# billdetect_ring2.net
KiCad netlist of a schematic drawn in EAGLE
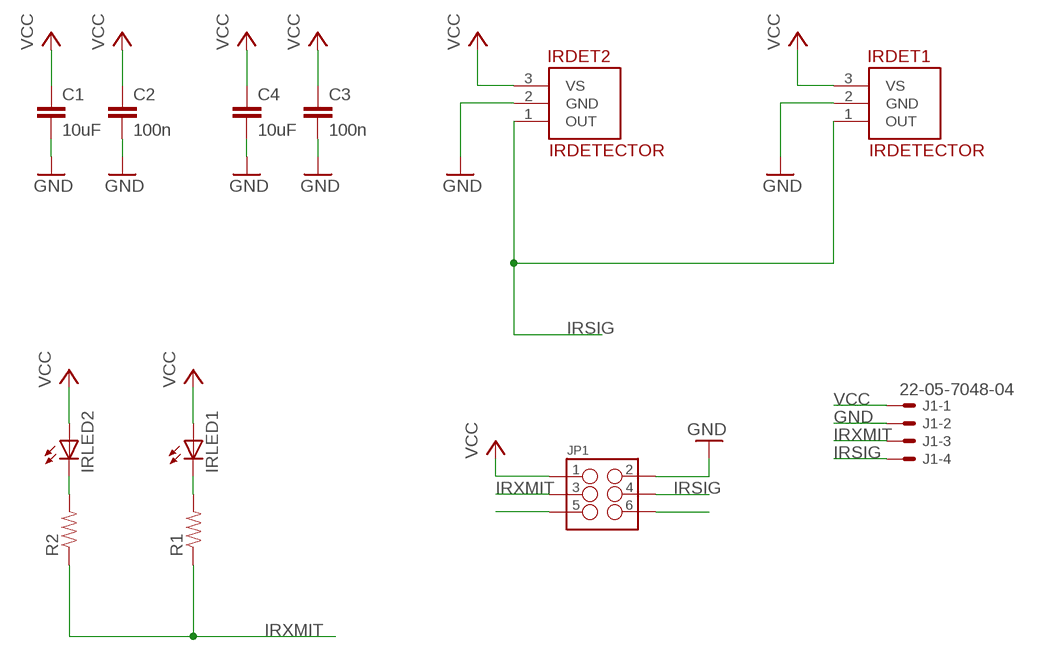
[diagram p0: schematic, sheet 1]

(export (version "E")
  (design (tool "Eeschema 10.0.6"))
  (components
    (comp (ref "C1")
      (value "10uF")
      (footprint "eagle-import:0805")
      (libsource (lib "eagle-import") (part "CAP0805"))
    )
    (comp (ref "C2")
      (value "100n")
      (footprint "eagle-import:0805")
      (libsource (lib "eagle-import") (part "CAP0805"))
    )
    (comp (ref "C3")
      (value "100n")
      (footprint "eagle-import:0805")
      (libsource (lib "eagle-import") (part "CAP0805"))
    )
    (comp (ref "C4")
      (value "10uF")
      (footprint "eagle-import:0805")
      (libsource (lib "eagle-import") (part "CAP0805"))
    )
    (comp (ref "IRDET1")
      (value "IRDETECTOR")
      (footprint "eagle-import:TSOP-3PIN-2.54MM")
      (libsource (lib "eagle-import") (part "IRDETECTOR"))
    )
    (comp (ref "IRDET2")
      (value "IRDETECTOR")
      (footprint "eagle-import:TSOP-3PIN-2.54MM")
      (libsource (lib "eagle-import") (part "IRDETECTOR"))
    )
    (comp (ref "IRLED1")
      (value "LED-5MM-90DEG")
      (footprint "eagle-import:LED-5MM-90DEG")
      (libsource (lib "eagle-import") (part "LED-5MM-90DEG"))
    )
    (comp (ref "IRLED2")
      (value "LED-5MM-90DEG")
      (footprint "eagle-import:LED-5MM-90DEG")
      (libsource (lib "eagle-import") (part "LED-5MM-90DEG"))
    )
    (comp (ref "J1")
      (value "22-05-7048-04")
      (footprint "eagle-import:7395-04")
      (libsource (lib "eagle-import") (part "22-?-0405-7048"))
    )
    (comp (ref "JP1")
      (value "M03X22X3_SILK_SM")
      (footprint "eagle-import:2X3")
      (libsource (lib "eagle-import") (part "M03X22X3_SILK_SM"))
    )
    (comp (ref "R1")
      (value "RESISTOR0805-RES")
      (footprint "eagle-import:0805")
      (libsource (lib "eagle-import") (part "RESISTOR0805-RES"))
    )
    (comp (ref "R2")
      (value "RESISTOR0805-RES")
      (footprint "eagle-import:0805")
      (libsource (lib "eagle-import") (part "RESISTOR0805-RES"))
    )
  )
  (nets
    (net (code "1") (name "/IRSIG") (class "Default")
      (node (ref "IRDET1") (pin "1") (pinfunction "OUT_1") (pintype "bidirectional"))
      (node (ref "IRDET2") (pin "1") (pinfunction "OUT_1") (pintype "bidirectional"))
      (node (ref "J1") (pin "4") (pinfunction "S_4") (pintype "passive"))
      (node (ref "JP1") (pin "4") (pinfunction "4_4") (pintype "bidirectional"))
    )
    (net (code "2") (name "/IRXMIT") (class "Default")
      (node (ref "J1") (pin "3") (pinfunction "S_3") (pintype "passive"))
      (node (ref "JP1") (pin "3") (pinfunction "3_3") (pintype "bidirectional"))
      (node (ref "R1") (pin "1") (pinfunction "1_1") (pintype "passive"))
      (node (ref "R2") (pin "1") (pinfunction "1_1") (pintype "passive"))
    )
    (net (code "3") (name "GND") (class "Default")
      (node (ref "C1") (pin "2") (pinfunction "2_2") (pintype "passive"))
      (node (ref "C2") (pin "2") (pinfunction "2_2") (pintype "passive"))
      (node (ref "C3") (pin "2") (pinfunction "2_2") (pintype "passive"))
      (node (ref "C4") (pin "2") (pinfunction "2_2") (pintype "passive"))
      (node (ref "IRDET1") (pin "2") (pinfunction "GND_2") (pintype "bidirectional"))
      (node (ref "IRDET2") (pin "2") (pinfunction "GND_2") (pintype "bidirectional"))
      (node (ref "J1") (pin "2") (pinfunction "S_2") (pintype "passive"))
      (node (ref "JP1") (pin "2") (pinfunction "2_2") (pintype "bidirectional"))
    )
    (net (code "4") (name "Net-(IRLED1-C)") (class "Default")
      (node (ref "IRLED1") (pin "K") (pinfunction "C_K") (pintype "passive"))
      (node (ref "R1") (pin "2") (pinfunction "2_2") (pintype "passive"))
    )
    (net (code "5") (name "Net-(IRLED2-C)") (class "Default")
      (node (ref "IRLED2") (pin "K") (pinfunction "C_K") (pintype "passive"))
      (node (ref "R2") (pin "2") (pinfunction "2_2") (pintype "passive"))
    )
    (net (code "6") (name "VCC") (class "Default")
      (node (ref "C1") (pin "1") (pinfunction "1_1") (pintype "passive"))
      (node (ref "C2") (pin "1") (pinfunction "1_1") (pintype "passive"))
      (node (ref "C3") (pin "1") (pinfunction "1_1") (pintype "passive"))
      (node (ref "C4") (pin "1") (pinfunction "1_1") (pintype "passive"))
      (node (ref "IRDET1") (pin "3") (pinfunction "VS_3") (pintype "bidirectional"))
      (node (ref "IRDET2") (pin "3") (pinfunction "VS_3") (pintype "bidirectional"))
      (node (ref "IRLED1") (pin "A") (pinfunction "A_A") (pintype "passive"))
      (node (ref "IRLED2") (pin "A") (pinfunction "A_A") (pintype "passive"))
      (node (ref "J1") (pin "1") (pinfunction "S_1") (pintype "passive"))
      (node (ref "JP1") (pin "1") (pinfunction "1_1") (pintype "bidirectional"))
    )
    (net (code "7") (name "unconnected-(JP1-Pad5)") (class "Default")
      (node (ref "JP1") (pin "5") (pinfunction "5_5") (pintype "bidirectional"))
    )
    (net (code "8") (name "unconnected-(JP1-Pad6)") (class "Default")
      (node (ref "JP1") (pin "6") (pinfunction "6_6") (pintype "bidirectional"))
    )
  )
)
